# controllerv2.net
KiCad netlist of a schematic drawn in EAGLE
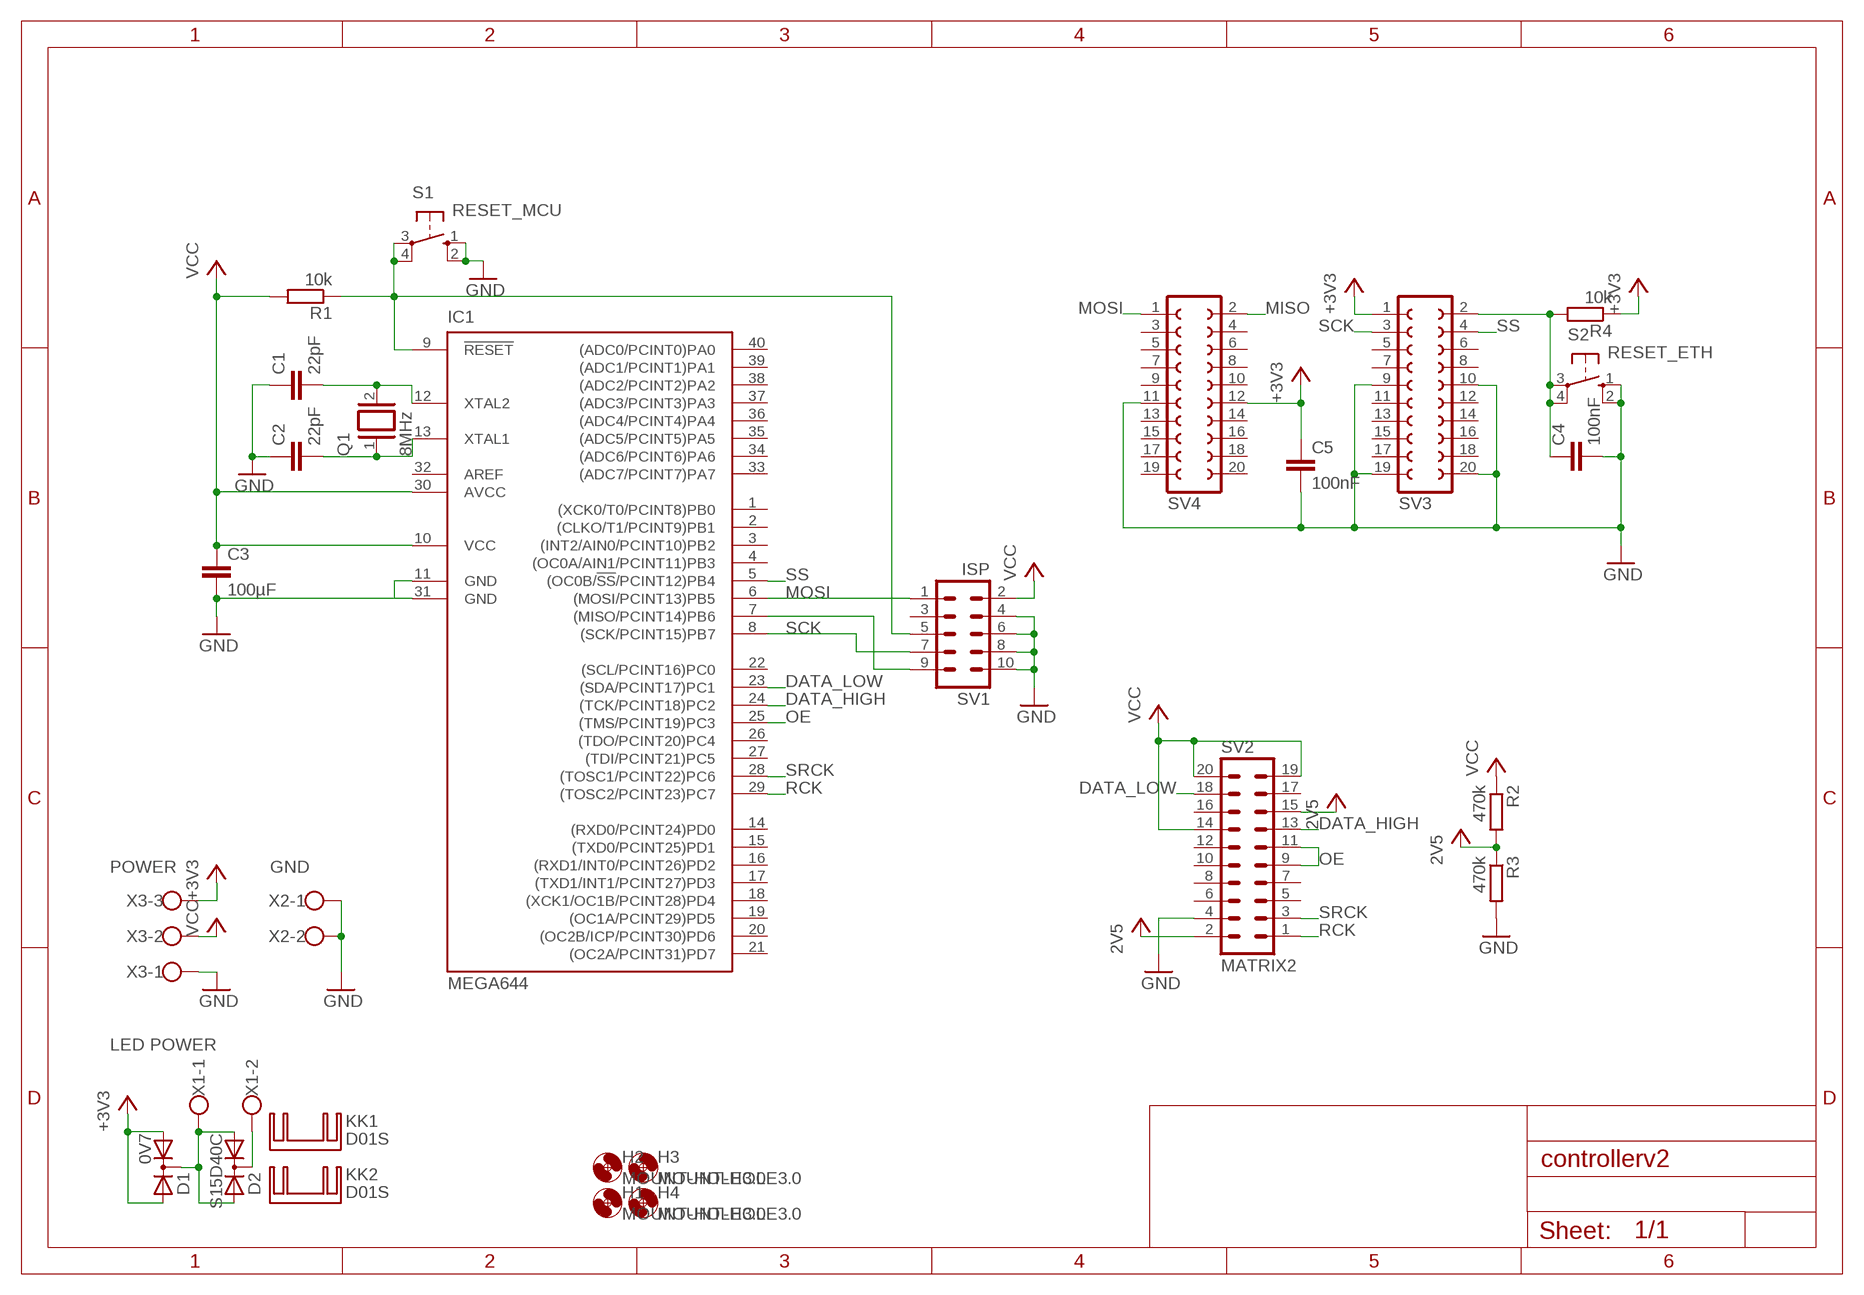
[diagram p0: schematic, sheet 1]

(export (version "E")
  (design (tool "Eeschema 10.0.6"))
  (components
    (comp (ref "C1")
      (value "22pF")
      (footprint "eagle-import:C050-024X044")
      (libsource (lib "eagle-import") (part "C-EU050-024X044"))
    )
    (comp (ref "C2")
      (value "22pF")
      (footprint "eagle-import:C050-024X044")
      (libsource (lib "eagle-import") (part "C-EU050-024X044"))
    )
    (comp (ref "C3")
      (value "100µF")
      (footprint "eagle-import:C050-030X075")
      (libsource (lib "eagle-import") (part "C-EU050-030X075"))
    )
    (comp (ref "C4")
      (value "100nF")
      (footprint "eagle-import:C050-024X044")
      (libsource (lib "eagle-import") (part "C-EU050-024X044"))
    )
    (comp (ref "C5")
      (value "100nF")
      (footprint "eagle-import:C050-024X044")
      (libsource (lib "eagle-import") (part "C-EU050-024X044"))
    )
    (comp (ref "D1")
      (value "0V7")
      (footprint "eagle-import:TO247BV")
      (libsource (lib "eagle-import") (part "S15D40C"))
    )
    (comp (ref "D2")
      (value "S15D40C")
      (footprint "eagle-import:TO247BV")
      (libsource (lib "eagle-import") (part "S15D40C"))
    )
    (comp (ref "H1")
      (value "MOUNT-HOLE3.0")
      (footprint "eagle-import:3,0")
      (libsource (lib "eagle-import") (part "MOUNT-HOLE3.0"))
    )
    (comp (ref "H2")
      (value "MOUNT-HOLE3.0")
      (footprint "eagle-import:3,0")
      (libsource (lib "eagle-import") (part "MOUNT-HOLE3.0"))
    )
    (comp (ref "H3")
      (value "MOUNT-HOLE3.0")
      (footprint "eagle-import:3,0")
      (libsource (lib "eagle-import") (part "MOUNT-HOLE3.0"))
    )
    (comp (ref "H4")
      (value "MOUNT-HOLE3.0")
      (footprint "eagle-import:3,0")
      (libsource (lib "eagle-import") (part "MOUNT-HOLE3.0"))
    )
    (comp (ref "IC1")
      (value "MEGA644")
      (footprint "eagle-import:DIL40")
      (libsource (lib "eagle-import") (part "MEGA164P/324P/644P-PU"))
    )
    (comp (ref "KK1")
      (value "D01S")
      (footprint "eagle-import:D01S")
      (libsource (lib "eagle-import") (part "D01S"))
    )
    (comp (ref "KK2")
      (value "D01S")
      (footprint "eagle-import:D01S")
      (libsource (lib "eagle-import") (part "D01S"))
    )
    (comp (ref "Q1")
      (value "8MHz")
      (footprint "eagle-import:QS")
      (libsource (lib "eagle-import") (part "XTAL/S"))
    )
    (comp (ref "R1")
      (value "10k")
      (footprint "eagle-import:0207_10")
      (libsource (lib "eagle-import") (part "R-EU_0207/10"))
    )
    (comp (ref "R2")
      (value "470k")
      (footprint "eagle-import:0207_10")
      (libsource (lib "eagle-import") (part "R-EU_0207/10"))
    )
    (comp (ref "R3")
      (value "470k")
      (footprint "eagle-import:0207_10")
      (libsource (lib "eagle-import") (part "R-EU_0207/10"))
    )
    (comp (ref "R4")
      (value "10k")
      (footprint "eagle-import:0207_10")
      (libsource (lib "eagle-import") (part "R-EU_0207/10"))
    )
    (comp (ref "S1")
      (value "RESET_MCU")
      (footprint "eagle-import:B3F-10XX")
      (fields (field (name "MPN") "B3F-1000"))
      (libsource (lib "eagle-import") (part "10-XX"))
    )
    (comp (ref "S2")
      (value "RESET_ETH")
      (footprint "eagle-import:B3F-10XX")
      (fields (field (name "MPN") "B3F-1000"))
      (libsource (lib "eagle-import") (part "10-XX"))
    )
    (comp (ref "SV1")
      (value "ISP")
      (footprint "eagle-import:ML10")
      (libsource (lib "eagle-import") (part "ML10"))
    )
    (comp (ref "SV2")
      (value "MATRIX2")
      (footprint "eagle-import:ML20")
      (libsource (lib "eagle-import") (part "ML20"))
    )
    (comp (ref "SV3")
      (value "FE10-2")
      (footprint "eagle-import:FE10-2")
      (libsource (lib "eagle-import") (part "FE10-2"))
    )
    (comp (ref "SV4")
      (value "FE10-2")
      (footprint "eagle-import:FE10-2")
      (libsource (lib "eagle-import") (part "FE10-2"))
    )
    (comp (ref "X1")
      (value "LED POWER")
      (footprint "eagle-import:W237-102")
      (fields (field (name "MPN") "237-102"))
      (libsource (lib "eagle-import") (part "W237-102"))
    )
    (comp (ref "X2")
      (value "GND")
      (footprint "eagle-import:W237-102")
      (fields (field (name "MPN") "237-102"))
      (libsource (lib "eagle-import") (part "W237-102"))
    )
    (comp (ref "X3")
      (value "POWER")
      (footprint "eagle-import:W237-103")
      (fields
        (field (name "MPN") "237-103")
        (field (name "MPN_1") "237-103")
        (field (name "OC_NEWARK") "18M7116")
      )
      (libsource (lib "eagle-import") (part "W237-103"))
    )
  )
  (nets
    (net (code "1") (name "+3V3") (class "Default")
      (node (ref "C5") (pin "1") (pinfunction "1_1") (pintype "passive"))
      (node (ref "D1") (pin "G") (pinfunction "A1_G") (pintype "passive"))
      (node (ref "D1") (pin "S") (pinfunction "A2_S") (pintype "passive"))
      (node (ref "R2") (pin "2") (pinfunction "2_2") (pintype "passive"))
      (node (ref "R3") (pin "1") (pinfunction "1_1") (pintype "passive"))
      (node (ref "R4") (pin "1") (pinfunction "1_1") (pintype "passive"))
      (node (ref "SV2") (pin "15") (pinfunction "15_15") (pintype "passive"))
      (node (ref "SV2") (pin "2") (pinfunction "2_2") (pintype "passive"))
      (node (ref "SV3") (pin "1") (pinfunction "1_1") (pintype "passive"))
      (node (ref "SV4") (pin "12") (pinfunction "12_12") (pintype "passive"))
      (node (ref "X3") (pin "3") (pinfunction "KL_3") (pintype "passive"))
    )
    (net (code "2") (name "/AREF") (class "Default")
      (node (ref "IC1") (pin "32") (pinfunction "AREF_32") (pintype "power_in"))
    )
    (net (code "3") (name "/DATA_HIGH") (class "Default")
      (node (ref "IC1") (pin "24") (pinfunction "(TCK/PCINT18)PC2_24") (pintype "bidirectional"))
      (node (ref "SV2") (pin "13") (pinfunction "13_13") (pintype "passive"))
    )
    (net (code "4") (name "/DATA_LOW") (class "Default")
      (node (ref "IC1") (pin "23") (pinfunction "(SDA/PCINT17)PC1_23") (pintype "bidirectional"))
      (node (ref "SV2") (pin "18") (pinfunction "18_18") (pintype "passive"))
    )
    (net (code "5") (name "/MISO") (class "Default")
      (node (ref "SV4") (pin "2") (pinfunction "2_2") (pintype "passive"))
    )
    (net (code "6") (name "/MOSI") (class "Default")
      (node (ref "IC1") (pin "6") (pinfunction "(MOSI/PCINT13)PB5_6") (pintype "bidirectional"))
      (node (ref "SV1") (pin "1") (pinfunction "1_1") (pintype "passive"))
      (node (ref "SV4") (pin "1") (pinfunction "1_1") (pintype "passive"))
    )
    (net (code "7") (name "/OE") (class "Default")
      (node (ref "IC1") (pin "25") (pinfunction "(TMS/PCINT19)PC3_25") (pintype "bidirectional"))
      (node (ref "SV2") (pin "11") (pinfunction "11_11") (pintype "passive"))
      (node (ref "SV2") (pin "9") (pinfunction "9_9") (pintype "passive"))
    )
    (net (code "8") (name "/RCK") (class "Default")
      (node (ref "IC1") (pin "29") (pinfunction "(TOSC2/PCINT23)PC7_29") (pintype "bidirectional"))
      (node (ref "SV2") (pin "1") (pinfunction "1_1") (pintype "passive"))
    )
    (net (code "9") (name "/SCK") (class "Default")
      (node (ref "IC1") (pin "8") (pinfunction "(SCK/PCINT15)PB7_8") (pintype "bidirectional"))
      (node (ref "SV1") (pin "7") (pinfunction "7_7") (pintype "passive"))
      (node (ref "SV3") (pin "3") (pinfunction "3_3") (pintype "passive"))
    )
    (net (code "10") (name "/SRCK") (class "Default")
      (node (ref "IC1") (pin "28") (pinfunction "(TOSC1/PCINT22)PC6_28") (pintype "bidirectional"))
      (node (ref "SV2") (pin "3") (pinfunction "3_3") (pintype "passive"))
    )
    (net (code "11") (name "/SS") (class "Default")
      (node (ref "IC1") (pin "5") (pinfunction "(OC0B/~{SS}/PCINT12)PB4_5") (pintype "bidirectional"))
      (node (ref "SV3") (pin "4") (pinfunction "4_4") (pintype "passive"))
    )
    (net (code "12") (name "GND") (class "Default")
      (node (ref "C1") (pin "1") (pinfunction "1_1") (pintype "passive"))
      (node (ref "C2") (pin "1") (pinfunction "1_1") (pintype "passive"))
      (node (ref "C3") (pin "2") (pinfunction "2_2") (pintype "passive"))
      (node (ref "C4") (pin "2") (pinfunction "2_2") (pintype "passive"))
      (node (ref "C5") (pin "2") (pinfunction "2_2") (pintype "passive"))
      (node (ref "IC1") (pin "11") (pinfunction "GND_11") (pintype "power_in"))
      (node (ref "IC1") (pin "31") (pinfunction "GND_31") (pintype "power_in"))
      (node (ref "R3") (pin "2") (pinfunction "2_2") (pintype "passive"))
      (node (ref "S1") (pin "1") (pinfunction "S_1") (pintype "passive"))
      (node (ref "S1") (pin "2") (pinfunction "S1_2") (pintype "passive"))
      (node (ref "S2") (pin "1") (pinfunction "S_1") (pintype "passive"))
      (node (ref "S2") (pin "2") (pinfunction "S1_2") (pintype "passive"))
      (node (ref "SV1") (pin "10") (pinfunction "10_10") (pintype "passive"))
      (node (ref "SV1") (pin "4") (pinfunction "4_4") (pintype "passive"))
      (node (ref "SV1") (pin "6") (pinfunction "6_6") (pintype "passive"))
      (node (ref "SV1") (pin "8") (pinfunction "8_8") (pintype "passive"))
      (node (ref "SV2") (pin "4") (pinfunction "4_4") (pintype "passive"))
      (node (ref "SV3") (pin "10") (pinfunction "10_10") (pintype "passive"))
      (node (ref "SV3") (pin "19") (pinfunction "19_19") (pintype "passive"))
      (node (ref "SV3") (pin "20") (pinfunction "20_20") (pintype "passive"))
      (node (ref "SV3") (pin "9") (pinfunction "9_9") (pintype "passive"))
      (node (ref "SV4") (pin "11") (pinfunction "11_11") (pintype "passive"))
      (node (ref "X2") (pin "1") (pinfunction "KL_1") (pintype "passive"))
      (node (ref "X2") (pin "2") (pinfunction "KL_2") (pintype "passive"))
      (node (ref "X3") (pin "1") (pinfunction "KL_1") (pintype "passive"))
    )
    (net (code "13") (name "Net-(D1-C)") (class "Default")
      (node (ref "D1") (pin "D") (pinfunction "C_D") (pintype "passive"))
      (node (ref "D2") (pin "G") (pinfunction "A1_G") (pintype "passive"))
      (node (ref "D2") (pin "S") (pinfunction "A2_S") (pintype "passive"))
      (node (ref "X1") (pin "1") (pinfunction "KL_1") (pintype "passive"))
    )
    (net (code "14") (name "Net-(D2-C)") (class "Default")
      (node (ref "D2") (pin "D") (pinfunction "C_D") (pintype "passive"))
      (node (ref "X1") (pin "2") (pinfunction "KL_2") (pintype "passive"))
    )
    (net (code "15") (name "Net-(IC1-(MISO{slash}PCINT14)PB6)") (class "Default")
      (node (ref "IC1") (pin "7") (pinfunction "(MISO/PCINT14)PB6_7") (pintype "bidirectional"))
      (node (ref "SV1") (pin "9") (pinfunction "9_9") (pintype "passive"))
    )
    (net (code "16") (name "Net-(IC1-XTAL1)") (class "Default")
      (node (ref "C2") (pin "2") (pinfunction "2_2") (pintype "passive"))
      (node (ref "IC1") (pin "13") (pinfunction "XTAL1_13") (pintype "input"))
      (node (ref "Q1") (pin "1") (pinfunction "1_1") (pintype "passive"))
    )
    (net (code "17") (name "Net-(IC1-XTAL2)") (class "Default")
      (node (ref "C1") (pin "2") (pinfunction "2_2") (pintype "passive"))
      (node (ref "IC1") (pin "12") (pinfunction "XTAL2_12") (pintype "output"))
      (node (ref "Q1") (pin "2") (pinfunction "2_2") (pintype "passive"))
    )
    (net (code "18") (name "Net-(IC1-~{RESET})") (class "Default")
      (node (ref "IC1") (pin "9") (pinfunction "~{RESET}_9") (pintype "input"))
      (node (ref "R1") (pin "1") (pinfunction "1_1") (pintype "passive"))
      (node (ref "S1") (pin "3") (pinfunction "P_3") (pintype "passive"))
      (node (ref "S1") (pin "4") (pinfunction "P1_4") (pintype "passive"))
      (node (ref "SV1") (pin "5") (pinfunction "5_5") (pintype "passive"))
    )
    (net (code "19") (name "Net-(S2-P)") (class "Default")
      (node (ref "C4") (pin "1") (pinfunction "1_1") (pintype "passive"))
      (node (ref "R4") (pin "2") (pinfunction "2_2") (pintype "passive"))
      (node (ref "S2") (pin "3") (pinfunction "P_3") (pintype "passive"))
      (node (ref "S2") (pin "4") (pinfunction "P1_4") (pintype "passive"))
      (node (ref "SV3") (pin "2") (pinfunction "2_2") (pintype "passive"))
    )
    (net (code "20") (name "VCC") (class "Default")
      (node (ref "C3") (pin "1") (pinfunction "1_1") (pintype "passive"))
      (node (ref "IC1") (pin "10") (pinfunction "VCC_10") (pintype "power_in"))
      (node (ref "IC1") (pin "30") (pinfunction "AVCC_30") (pintype "power_in"))
      (node (ref "R1") (pin "2") (pinfunction "2_2") (pintype "passive"))
      (node (ref "R2") (pin "1") (pinfunction "1_1") (pintype "passive"))
      (node (ref "SV1") (pin "2") (pinfunction "2_2") (pintype "passive"))
      (node (ref "SV2") (pin "14") (pinfunction "14_14") (pintype "passive"))
      (node (ref "SV2") (pin "19") (pinfunction "19_19") (pintype "passive"))
      (node (ref "SV2") (pin "20") (pinfunction "20_20") (pintype "passive"))
      (node (ref "X3") (pin "2") (pinfunction "KL_2") (pintype "passive"))
    )
    (net (code "21") (name "unconnected-(IC1-(ADC0{slash}PCINT0)PA0-Pad40)") (class "Default")
      (node (ref "IC1") (pin "40") (pinfunction "(ADC0/PCINT0)PA0_40") (pintype "bidirectional"))
    )
    (net (code "22") (name "unconnected-(IC1-(ADC1{slash}PCINT1)PA1-Pad39)") (class "Default")
      (node (ref "IC1") (pin "39") (pinfunction "(ADC1/PCINT1)PA1_39") (pintype "bidirectional"))
    )
    (net (code "23") (name "unconnected-(IC1-(ADC2{slash}PCINT2)PA2-Pad38)") (class "Default")
      (node (ref "IC1") (pin "38") (pinfunction "(ADC2/PCINT2)PA2_38") (pintype "bidirectional"))
    )
    (net (code "24") (name "unconnected-(IC1-(ADC3{slash}PCINT3)PA3-Pad37)") (class "Default")
      (node (ref "IC1") (pin "37") (pinfunction "(ADC3/PCINT3)PA3_37") (pintype "bidirectional"))
    )
    (net (code "25") (name "unconnected-(IC1-(ADC4{slash}PCINT4)PA4-Pad36)") (class "Default")
      (node (ref "IC1") (pin "36") (pinfunction "(ADC4/PCINT4)PA4_36") (pintype "bidirectional"))
    )
    (net (code "26") (name "unconnected-(IC1-(ADC5{slash}PCINT5)PA5-Pad35)") (class "Default")
      (node (ref "IC1") (pin "35") (pinfunction "(ADC5/PCINT5)PA5_35") (pintype "bidirectional"))
    )
    (net (code "27") (name "unconnected-(IC1-(ADC6{slash}PCINT6)PA6-Pad34)") (class "Default")
      (node (ref "IC1") (pin "34") (pinfunction "(ADC6/PCINT6)PA6_34") (pintype "bidirectional"))
    )
    (net (code "28") (name "unconnected-(IC1-(ADC7{slash}PCINT7)PA7-Pad33)") (class "Default")
      (node (ref "IC1") (pin "33") (pinfunction "(ADC7/PCINT7)PA7_33") (pintype "bidirectional"))
    )
    (net (code "29") (name "unconnected-(IC1-(CLKO{slash}T1{slash}PCINT9)PB1-Pad2)") (class "Default")
      (node (ref "IC1") (pin "2") (pinfunction "(CLKO/T1/PCINT9)PB1_2") (pintype "bidirectional"))
    )
    (net (code "30") (name "unconnected-(IC1-(INT2{slash}AIN0{slash}PCINT10)PB2-Pad3)") (class "Default")
      (node (ref "IC1") (pin "3") (pinfunction "(INT2/AIN0/PCINT10)PB2_3") (pintype "bidirectional"))
    )
    (net (code "31") (name "unconnected-(IC1-(OC0A{slash}AIN1{slash}PCINT11)PB3-Pad4)") (class "Default")
      (node (ref "IC1") (pin "4") (pinfunction "(OC0A/AIN1/PCINT11)PB3_4") (pintype "bidirectional"))
    )
    (net (code "32") (name "unconnected-(IC1-(OC1A{slash}PCINT29)PD5-Pad19)") (class "Default")
      (node (ref "IC1") (pin "19") (pinfunction "(OC1A/PCINT29)PD5_19") (pintype "bidirectional"))
    )
    (net (code "33") (name "unconnected-(IC1-(OC2A{slash}PCINT31)PD7-Pad21)") (class "Default")
      (node (ref "IC1") (pin "21") (pinfunction "(OC2A/PCINT31)PD7_21") (pintype "bidirectional"))
    )
    (net (code "34") (name "unconnected-(IC1-(OC2B{slash}ICP{slash}PCINT30)PD6-Pad20)") (class "Default")
      (node (ref "IC1") (pin "20") (pinfunction "(OC2B/ICP/PCINT30)PD6_20") (pintype "bidirectional"))
    )
    (net (code "35") (name "unconnected-(IC1-(RXD0{slash}PCINT24)PD0-Pad14)") (class "Default")
      (node (ref "IC1") (pin "14") (pinfunction "(RXD0/PCINT24)PD0_14") (pintype "bidirectional"))
    )
    (net (code "36") (name "unconnected-(IC1-(RXD1{slash}INT0{slash}PCINT26)PD2-Pad16)") (class "Default")
      (node (ref "IC1") (pin "16") (pinfunction "(RXD1/INT0/PCINT26)PD2_16") (pintype "bidirectional"))
    )
    (net (code "37") (name "unconnected-(IC1-(SCL{slash}PCINT16)PC0-Pad22)") (class "Default")
      (node (ref "IC1") (pin "22") (pinfunction "(SCL/PCINT16)PC0_22") (pintype "bidirectional"))
    )
    (net (code "38") (name "unconnected-(IC1-(TDI{slash}PCINT21)PC5-Pad27)") (class "Default")
      (node (ref "IC1") (pin "27") (pinfunction "(TDI/PCINT21)PC5_27") (pintype "bidirectional"))
    )
    (net (code "39") (name "unconnected-(IC1-(TDO{slash}PCINT20)PC4-Pad26)") (class "Default")
      (node (ref "IC1") (pin "26") (pinfunction "(TDO/PCINT20)PC4_26") (pintype "bidirectional"))
    )
    (net (code "40") (name "unconnected-(IC1-(TXD0{slash}PCINT25)PD1-Pad15)") (class "Default")
      (node (ref "IC1") (pin "15") (pinfunction "(TXD0/PCINT25)PD1_15") (pintype "bidirectional"))
    )
    (net (code "41") (name "unconnected-(IC1-(TXD1{slash}INT1{slash}PCINT27)PD3-Pad17)") (class "Default")
      (node (ref "IC1") (pin "17") (pinfunction "(TXD1/INT1/PCINT27)PD3_17") (pintype "bidirectional"))
    )
    (net (code "42") (name "unconnected-(IC1-(XCK0{slash}T0{slash}PCINT8)PB0-Pad1)") (class "Default")
      (node (ref "IC1") (pin "1") (pinfunction "(XCK0/T0/PCINT8)PB0_1") (pintype "bidirectional"))
    )
    (net (code "43") (name "unconnected-(IC1-(XCK1{slash}OC1B{slash}PCINT28)PD4-Pad18)") (class "Default")
      (node (ref "IC1") (pin "18") (pinfunction "(XCK1/OC1B/PCINT28)PD4_18") (pintype "bidirectional"))
    )
    (net (code "44") (name "unconnected-(SV1-Pad3)") (class "Default")
      (node (ref "SV1") (pin "3") (pinfunction "3_3") (pintype "passive"))
    )
    (net (code "45") (name "unconnected-(SV2-Pad5)") (class "Default")
      (node (ref "SV2") (pin "5") (pinfunction "5_5") (pintype "passive"))
    )
    (net (code "46") (name "unconnected-(SV2-Pad6)") (class "Default")
      (node (ref "SV2") (pin "6") (pinfunction "6_6") (pintype "passive"))
    )
    (net (code "47") (name "unconnected-(SV2-Pad7)") (class "Default")
      (node (ref "SV2") (pin "7") (pinfunction "7_7") (pintype "passive"))
    )
    (net (code "48") (name "unconnected-(SV2-Pad8)") (class "Default")
      (node (ref "SV2") (pin "8") (pinfunction "8_8") (pintype "passive"))
    )
    (net (code "49") (name "unconnected-(SV2-Pad10)") (class "Default")
      (node (ref "SV2") (pin "10") (pinfunction "10_10") (pintype "passive"))
    )
    (net (code "50") (name "unconnected-(SV2-Pad12)") (class "Default")
      (node (ref "SV2") (pin "12") (pinfunction "12_12") (pintype "passive"))
    )
    (net (code "51") (name "unconnected-(SV2-Pad16)") (class "Default")
      (node (ref "SV2") (pin "16") (pinfunction "16_16") (pintype "passive"))
    )
    (net (code "52") (name "unconnected-(SV2-Pad17)") (class "Default")
      (node (ref "SV2") (pin "17") (pinfunction "17_17") (pintype "passive"))
    )
    (net (code "53") (name "unconnected-(SV3-Pad5)") (class "Default")
      (node (ref "SV3") (pin "5") (pinfunction "5_5") (pintype "passive"))
    )
    (net (code "54") (name "unconnected-(SV3-Pad6)") (class "Default")
      (node (ref "SV3") (pin "6") (pinfunction "6_6") (pintype "passive"))
    )
    (net (code "55") (name "unconnected-(SV3-Pad7)") (class "Default")
      (node (ref "SV3") (pin "7") (pinfunction "7_7") (pintype "passive"))
    )
    (net (code "56") (name "unconnected-(SV3-Pad8)") (class "Default")
      (node (ref "SV3") (pin "8") (pinfunction "8_8") (pintype "passive"))
    )
    (net (code "57") (name "unconnected-(SV3-Pad11)") (class "Default")
      (node (ref "SV3") (pin "11") (pinfunction "11_11") (pintype "passive"))
    )
    (net (code "58") (name "unconnected-(SV3-Pad12)") (class "Default")
      (node (ref "SV3") (pin "12") (pinfunction "12_12") (pintype "passive"))
    )
    (net (code "59") (name "unconnected-(SV3-Pad13)") (class "Default")
      (node (ref "SV3") (pin "13") (pinfunction "13_13") (pintype "passive"))
    )
    (net (code "60") (name "unconnected-(SV3-Pad14)") (class "Default")
      (node (ref "SV3") (pin "14") (pinfunction "14_14") (pintype "passive"))
    )
    (net (code "61") (name "unconnected-(SV3-Pad15)") (class "Default")
      (node (ref "SV3") (pin "15") (pinfunction "15_15") (pintype "passive"))
    )
    (net (code "62") (name "unconnected-(SV3-Pad16)") (class "Default")
      (node (ref "SV3") (pin "16") (pinfunction "16_16") (pintype "passive"))
    )
    (net (code "63") (name "unconnected-(SV3-Pad17)") (class "Default")
      (node (ref "SV3") (pin "17") (pinfunction "17_17") (pintype "passive"))
    )
    (net (code "64") (name "unconnected-(SV3-Pad18)") (class "Default")
      (node (ref "SV3") (pin "18") (pinfunction "18_18") (pintype "passive"))
    )
    (net (code "65") (name "unconnected-(SV4-Pad3)") (class "Default")
      (node (ref "SV4") (pin "3") (pinfunction "3_3") (pintype "passive"))
    )
    (net (code "66") (name "unconnected-(SV4-Pad4)") (class "Default")
      (node (ref "SV4") (pin "4") (pinfunction "4_4") (pintype "passive"))
    )
    (net (code "67") (name "unconnected-(SV4-Pad5)") (class "Default")
      (node (ref "SV4") (pin "5") (pinfunction "5_5") (pintype "passive"))
    )
    (net (code "68") (name "unconnected-(SV4-Pad6)") (class "Default")
      (node (ref "SV4") (pin "6") (pinfunction "6_6") (pintype "passive"))
    )
    (net (code "69") (name "unconnected-(SV4-Pad7)") (class "Default")
      (node (ref "SV4") (pin "7") (pinfunction "7_7") (pintype "passive"))
    )
    (net (code "70") (name "unconnected-(SV4-Pad8)") (class "Default")
      (node (ref "SV4") (pin "8") (pinfunction "8_8") (pintype "passive"))
    )
    (net (code "71") (name "unconnected-(SV4-Pad9)") (class "Default")
      (node (ref "SV4") (pin "9") (pinfunction "9_9") (pintype "passive"))
    )
    (net (code "72") (name "unconnected-(SV4-Pad10)") (class "Default")
      (node (ref "SV4") (pin "10") (pinfunction "10_10") (pintype "passive"))
    )
    (net (code "73") (name "unconnected-(SV4-Pad13)") (class "Default")
      (node (ref "SV4") (pin "13") (pinfunction "13_13") (pintype "passive"))
    )
    (net (code "74") (name "unconnected-(SV4-Pad14)") (class "Default")
      (node (ref "SV4") (pin "14") (pinfunction "14_14") (pintype "passive"))
    )
    (net (code "75") (name "unconnected-(SV4-Pad15)") (class "Default")
      (node (ref "SV4") (pin "15") (pinfunction "15_15") (pintype "passive"))
    )
    (net (code "76") (name "unconnected-(SV4-Pad16)") (class "Default")
      (node (ref "SV4") (pin "16") (pinfunction "16_16") (pintype "passive"))
    )
    (net (code "77") (name "unconnected-(SV4-Pad17)") (class "Default")
      (node (ref "SV4") (pin "17") (pinfunction "17_17") (pintype "passive"))
    )
    (net (code "78") (name "unconnected-(SV4-Pad18)") (class "Default")
      (node (ref "SV4") (pin "18") (pinfunction "18_18") (pintype "passive"))
    )
    (net (code "79") (name "unconnected-(SV4-Pad19)") (class "Default")
      (node (ref "SV4") (pin "19") (pinfunction "19_19") (pintype "passive"))
    )
    (net (code "80") (name "unconnected-(SV4-Pad20)") (class "Default")
      (node (ref "SV4") (pin "20") (pinfunction "20_20") (pintype "passive"))
    )
  )
)
